# mbmc_single_board.net
KiCad netlist of a schematic drawn in EAGLE
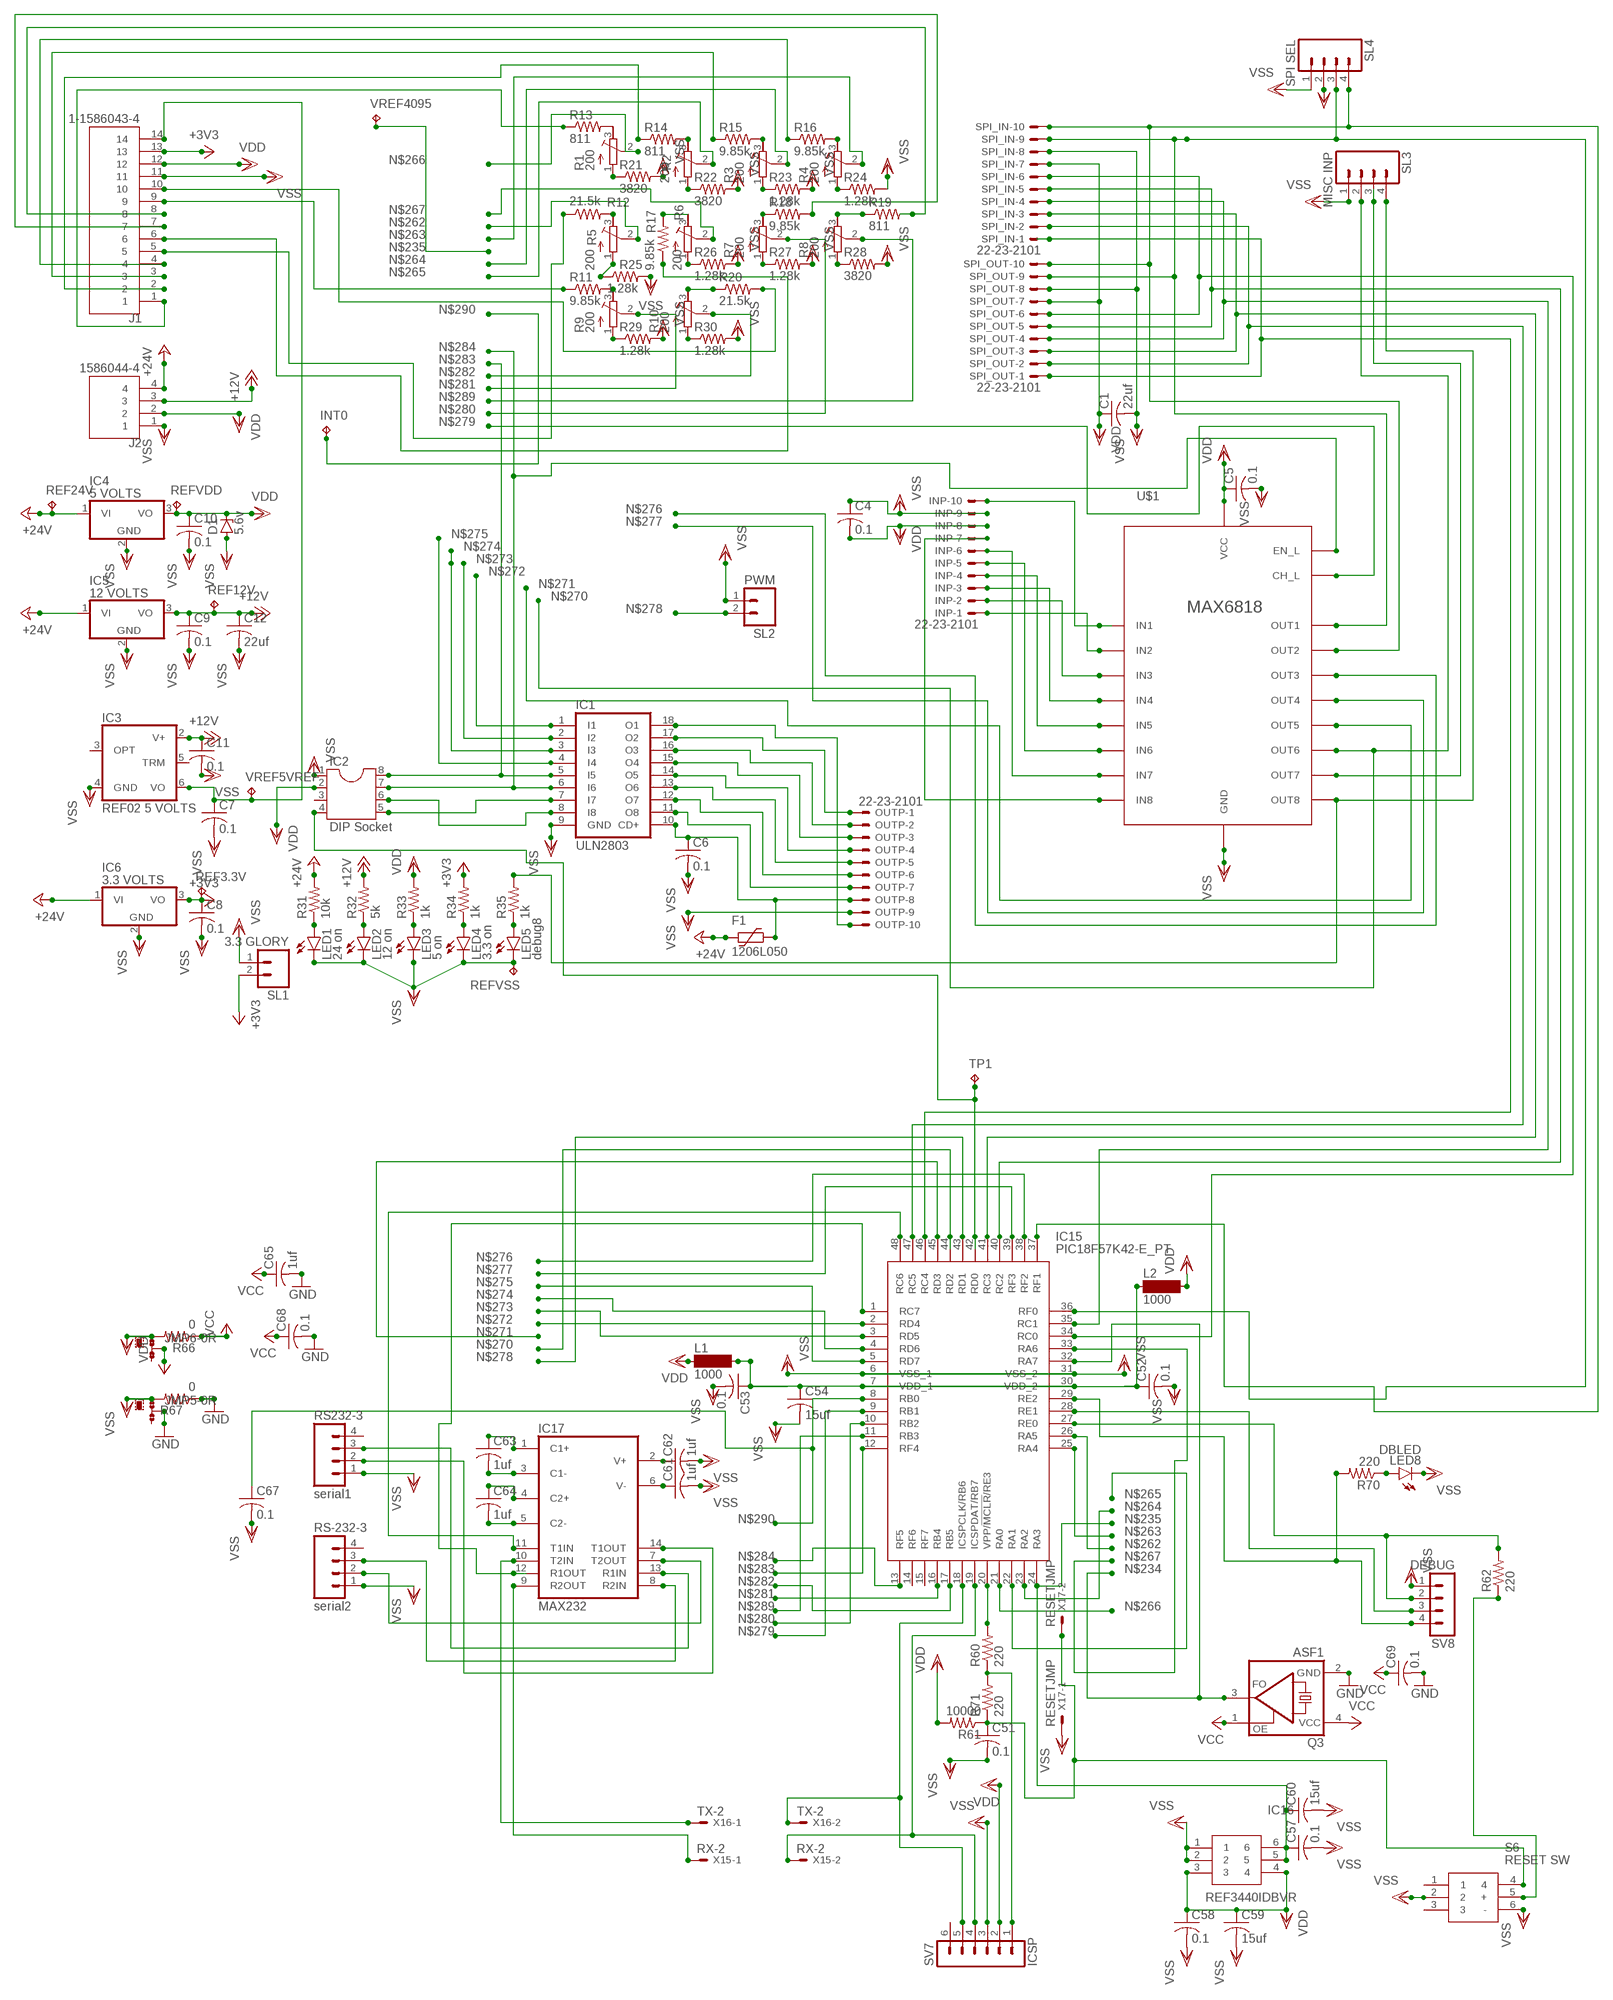
[diagram p0: schematic, sheet 1]

(export (version "E")
  (design (tool "Eeschema 10.0.6"))
  (components
    (comp (ref "C1")
      (value "22uf")
      (footprint "eagle-import:C0805")
      (libsource (lib "eagle-import") (part "C-USC0805"))
    )
    (comp (ref "C4")
      (value "0.1")
      (footprint "eagle-import:C0805")
      (libsource (lib "eagle-import") (part "C-USC0805"))
    )
    (comp (ref "C5")
      (value "0.1")
      (footprint "eagle-import:C0805")
      (libsource (lib "eagle-import") (part "C-USC0805"))
    )
    (comp (ref "C6")
      (value "0.1")
      (footprint "eagle-import:C0805")
      (libsource (lib "eagle-import") (part "C-USC0805"))
    )
    (comp (ref "C7")
      (value "0.1")
      (footprint "eagle-import:C0805")
      (libsource (lib "eagle-import") (part "C-USC0805"))
    )
    (comp (ref "C8")
      (value "0.1")
      (footprint "eagle-import:C0805")
      (libsource (lib "eagle-import") (part "C-USC0805"))
    )
    (comp (ref "C9")
      (value "0.1")
      (footprint "eagle-import:C0805")
      (libsource (lib "eagle-import") (part "C-USC0805"))
    )
    (comp (ref "C10")
      (value "0.1")
      (footprint "eagle-import:C0805")
      (libsource (lib "eagle-import") (part "C-USC0805"))
    )
    (comp (ref "C11")
      (value "0.1")
      (footprint "eagle-import:C0805")
      (libsource (lib "eagle-import") (part "C-USC0805"))
    )
    (comp (ref "C12")
      (value "22uf")
      (footprint "eagle-import:C0805")
      (libsource (lib "eagle-import") (part "C-USC0805"))
    )
    (comp (ref "C51")
      (value "0.1")
      (footprint "eagle-import:C1206")
      (libsource (lib "eagle-import") (part "C-USC1206"))
    )
    (comp (ref "C52")
      (value "0.1")
      (footprint "eagle-import:C1206")
      (libsource (lib "eagle-import") (part "C-USC1206"))
    )
    (comp (ref "C53")
      (value "0.1")
      (footprint "eagle-import:C1206")
      (libsource (lib "eagle-import") (part "C-USC1206"))
    )
    (comp (ref "C54")
      (value "15uf")
      (footprint "eagle-import:C1206")
      (libsource (lib "eagle-import") (part "C-USC1206"))
    )
    (comp (ref "C57")
      (value "0.1")
      (footprint "eagle-import:C1206")
      (libsource (lib "eagle-import") (part "C-USC1206"))
    )
    (comp (ref "C58")
      (value "0.1")
      (footprint "eagle-import:C1206")
      (libsource (lib "eagle-import") (part "C-USC1206"))
    )
    (comp (ref "C59")
      (value "15uf")
      (footprint "eagle-import:C1206")
      (libsource (lib "eagle-import") (part "C-USC1206"))
    )
    (comp (ref "C60")
      (value "15uf")
      (footprint "eagle-import:C1206")
      (libsource (lib "eagle-import") (part "C-USC1206"))
    )
    (comp (ref "C61")
      (value "1uf")
      (footprint "eagle-import:C0805")
      (libsource (lib "eagle-import") (part "C-USC0805"))
    )
    (comp (ref "C62")
      (value "1uf")
      (footprint "eagle-import:C0805")
      (libsource (lib "eagle-import") (part "C-USC0805"))
    )
    (comp (ref "C63")
      (value "1uf")
      (footprint "eagle-import:C0805")
      (libsource (lib "eagle-import") (part "C-USC0805"))
    )
    (comp (ref "C64")
      (value "1uf")
      (footprint "eagle-import:C0805")
      (libsource (lib "eagle-import") (part "C-USC0805"))
    )
    (comp (ref "C65")
      (value "1uf")
      (footprint "eagle-import:C0805")
      (libsource (lib "eagle-import") (part "C-USC0805"))
    )
    (comp (ref "C67")
      (value "0.1")
      (footprint "eagle-import:C1206")
      (libsource (lib "eagle-import") (part "C-USC1206"))
    )
    (comp (ref "C68")
      (value "0.1")
      (footprint "eagle-import:C1206")
      (libsource (lib "eagle-import") (part "C-USC1206"))
    )
    (comp (ref "C69")
      (value "0.1")
      (footprint "eagle-import:C1206")
      (libsource (lib "eagle-import") (part "C-USC1206"))
    )
    (comp (ref "D1")
      (value "5.6v")
      (footprint "eagle-import:ZDIO-2.5")
      (libsource (lib "eagle-import") (part "ZENER-DIODEZD-2.5"))
    )
    (comp (ref "F1")
      (value "1206L050")
      (footprint "eagle-import:1206L")
      (fields (field (name "MF") "Littelfuse"))
      (libsource (lib "eagle-import") (part "?1206L050"))
    )
    (comp (ref "IC1")
      (value "ULN2803")
      (footprint "eagle-import:DIL18")
      (libsource (lib "eagle-import") (part "ULN2803A"))
    )
    (comp (ref "IC2")
      (value "DIP Socket")
      (footprint "eagle-import:SOCKET-08")
      (libsource (lib "eagle-import") (part "DIL8S"))
    )
    (comp (ref "IC3")
      (value "REF02 5 VOLTS")
      (footprint "eagle-import:DIL08")
      (libsource (lib "eagle-import") (part "REF02Z"))
    )
    (comp (ref "IC4")
      (value "5 VOLTS")
      (footprint "eagle-import:TO220V")
      (libsource (lib "eagle-import") (part "78TV05"))
    )
    (comp (ref "IC5")
      (value "12 VOLTS")
      (footprint "eagle-import:TO220V")
      (libsource (lib "eagle-import") (part "78TV05"))
    )
    (comp (ref "IC6")
      (value "3.3 VOLTS")
      (footprint "eagle-import:TO220V")
      (libsource (lib "eagle-import") (part "78TV05"))
    )
    (comp (ref "IC15")
      (value "PIC18F57K42-E_PT")
      (footprint "eagle-import:QFP50P900X900X120-48N")
      (fields
        (field (name "MANUFACTURER_PART_NUMBER") "PIC18F57K42-E/PT")
        (field (name "MOUSER_PART_NUMBER") "579-PIC18F57K42-E/PT")
      )
      (libsource (lib "eagle-import") (part "PIC18F57K42-E_PT"))
    )
    (comp (ref "IC16")
      (value "REF3440IDBVR")
      (footprint "eagle-import:SOP95P280X145-6N")
      (libsource (lib "eagle-import") (part "REF3440IDBVR"))
    )
    (comp (ref "IC17")
      (value "MAX232")
      (footprint "eagle-import:DIL16")
      (fields (field (name "MF") "MAXIM") (field (name "MPN") "MAX232ACPE+"))
      (libsource (lib "eagle-import") (part "MAX232"))
    )
    (comp (ref "INP")
      (value "22-23-2101")
      (footprint "eagle-import:22-23-2101")
      (fields (field (name "MF") "MOLEX"))
      (libsource (lib "eagle-import") (part "22-23-2101"))
    )
    (comp (ref "INT0")
      (value "TPB1,27")
      (footprint "eagle-import:B1,27")
      (libsource (lib "eagle-import") (part "TPB1,27"))
    )
    (comp (ref "J1")
      (value "1-1586043-4")
      (footprint "eagle-import:TE_1-1586043-4")
      (fields (field (name "MANUFACTURER") "TE"))
      (libsource (lib "eagle-import") (part "1-1586043-4"))
    )
    (comp (ref "J2")
      (value "1586044-4")
      (footprint "eagle-import:TE_1586044-4")
      (fields (field (name "MANUFACTURER") "TE"))
      (libsource (lib "eagle-import") (part "1586044-4"))
    )
    (comp (ref "JMP5")
      (value "0R-JUMPA")
      (footprint "eagle-import:A0R-JMP")
      (libsource (lib "eagle-import") (part "0R-JUMPA"))
    )
    (comp (ref "JMP6")
      (value "0R-JUMPA")
      (footprint "eagle-import:A0R-JMP")
      (libsource (lib "eagle-import") (part "0R-JUMPA"))
    )
    (comp (ref "L1")
      (value "1000")
      (footprint "eagle-import:SM-1206")
      (libsource (lib "eagle-import") (part "SM-1206"))
    )
    (comp (ref "L2")
      (value "1000")
      (footprint "eagle-import:SM-1206")
      (libsource (lib "eagle-import") (part "SM-1206"))
    )
    (comp (ref "LED1")
      (value "24 on")
      (footprint "eagle-import:CHIPLED_1206")
      (libsource (lib "eagle-import") (part "LEDCHIPLED_1206"))
    )
    (comp (ref "LED2")
      (value "12 on")
      (footprint "eagle-import:CHIPLED_1206")
      (libsource (lib "eagle-import") (part "LEDCHIPLED_1206"))
    )
    (comp (ref "LED3")
      (value "5 on")
      (footprint "eagle-import:CHIPLED_1206")
      (libsource (lib "eagle-import") (part "LEDCHIPLED_1206"))
    )
    (comp (ref "LED4")
      (value "3.3 on")
      (footprint "eagle-import:CHIPLED_1206")
      (libsource (lib "eagle-import") (part "LEDCHIPLED_1206"))
    )
    (comp (ref "LED5")
      (value "debug8")
      (footprint "eagle-import:CHIPLED_1206")
      (libsource (lib "eagle-import") (part "LEDCHIPLED_1206"))
    )
    (comp (ref "LED8")
      (value "DBLED")
      (footprint "eagle-import:CHIPLED_1206")
      (libsource (lib "eagle-import") (part "LEDCHIPLED_1206"))
    )
    (comp (ref "OUTP")
      (value "22-23-2101")
      (footprint "eagle-import:22-23-2101")
      (fields (field (name "MF") "MOLEX"))
      (libsource (lib "eagle-import") (part "22-23-2101"))
    )
    (comp (ref "Q3")
      (value "ASF1")
      (footprint "eagle-import:ASF")
      (libsource (lib "eagle-import") (part "ASF1"))
    )
    (comp (ref "R1")
      (value "200")
      (footprint "eagle-import:RTRIM3339P")
      (libsource (lib "eagle-import") (part "R-TRIMM3339P"))
    )
    (comp (ref "R2")
      (value "200")
      (footprint "eagle-import:RTRIM3339P")
      (libsource (lib "eagle-import") (part "R-TRIMM3339P"))
    )
    (comp (ref "R3")
      (value "200")
      (footprint "eagle-import:RTRIM3339P")
      (libsource (lib "eagle-import") (part "R-TRIMM3339P"))
    )
    (comp (ref "R4")
      (value "200")
      (footprint "eagle-import:RTRIM3339P")
      (libsource (lib "eagle-import") (part "R-TRIMM3339P"))
    )
    (comp (ref "R5")
      (value "200")
      (footprint "eagle-import:RTRIM3339P")
      (libsource (lib "eagle-import") (part "R-TRIMM3339P"))
    )
    (comp (ref "R6")
      (value "200")
      (footprint "eagle-import:RTRIM3339P")
      (libsource (lib "eagle-import") (part "R-TRIMM3339P"))
    )
    (comp (ref "R7")
      (value "200")
      (footprint "eagle-import:RTRIM3339P")
      (libsource (lib "eagle-import") (part "R-TRIMM3339P"))
    )
    (comp (ref "R8")
      (value "200")
      (footprint "eagle-import:RTRIM3339P")
      (libsource (lib "eagle-import") (part "R-TRIMM3339P"))
    )
    (comp (ref "R9")
      (value "200")
      (footprint "eagle-import:RTRIM3339P")
      (libsource (lib "eagle-import") (part "R-TRIMM3339P"))
    )
    (comp (ref "R10")
      (value "200")
      (footprint "eagle-import:RTRIM3339P")
      (libsource (lib "eagle-import") (part "R-TRIMM3339P"))
    )
    (comp (ref "R11")
      (value "9.85k")
      (footprint "eagle-import:R0805")
      (libsource (lib "eagle-import") (part "R-US_R0805"))
    )
    (comp (ref "R12")
      (value "21.5k")
      (footprint "eagle-import:R0805")
      (libsource (lib "eagle-import") (part "R-US_R0805"))
    )
    (comp (ref "R13")
      (value "811")
      (footprint "eagle-import:R0805")
      (libsource (lib "eagle-import") (part "R-US_R0805"))
    )
    (comp (ref "R14")
      (value "811")
      (footprint "eagle-import:R0805")
      (libsource (lib "eagle-import") (part "R-US_R0805"))
    )
    (comp (ref "R15")
      (value "9.85k")
      (footprint "eagle-import:R0805")
      (libsource (lib "eagle-import") (part "R-US_R0805"))
    )
    (comp (ref "R16")
      (value "9.85k")
      (footprint "eagle-import:R0805")
      (libsource (lib "eagle-import") (part "R-US_R0805"))
    )
    (comp (ref "R17")
      (value "9.85k")
      (footprint "eagle-import:R0805")
      (libsource (lib "eagle-import") (part "R-US_R0805"))
    )
    (comp (ref "R18")
      (value "9.85k")
      (footprint "eagle-import:R0805")
      (libsource (lib "eagle-import") (part "R-US_R0805"))
    )
    (comp (ref "R19")
      (value "811")
      (footprint "eagle-import:R0805")
      (libsource (lib "eagle-import") (part "R-US_R0805"))
    )
    (comp (ref "R20")
      (value "21.5k")
      (footprint "eagle-import:R0805")
      (libsource (lib "eagle-import") (part "R-US_R0805"))
    )
    (comp (ref "R21")
      (value "3820")
      (footprint "eagle-import:R0805")
      (libsource (lib "eagle-import") (part "R-US_R0805"))
    )
    (comp (ref "R22")
      (value "3820")
      (footprint "eagle-import:R0805")
      (libsource (lib "eagle-import") (part "R-US_R0805"))
    )
    (comp (ref "R23")
      (value "1.28k")
      (footprint "eagle-import:R0805")
      (libsource (lib "eagle-import") (part "R-US_R0805"))
    )
    (comp (ref "R24")
      (value "1.28k")
      (footprint "eagle-import:R0805")
      (libsource (lib "eagle-import") (part "R-US_R0805"))
    )
    (comp (ref "R25")
      (value "1.28k")
      (footprint "eagle-import:R0805")
      (libsource (lib "eagle-import") (part "R-US_R0805"))
    )
    (comp (ref "R26")
      (value "1.28k")
      (footprint "eagle-import:R0805")
      (libsource (lib "eagle-import") (part "R-US_R0805"))
    )
    (comp (ref "R27")
      (value "1.28k")
      (footprint "eagle-import:R0805")
      (libsource (lib "eagle-import") (part "R-US_R0805"))
    )
    (comp (ref "R28")
      (value "3820")
      (footprint "eagle-import:R0805")
      (libsource (lib "eagle-import") (part "R-US_R0805"))
    )
    (comp (ref "R29")
      (value "1.28k")
      (footprint "eagle-import:R0805")
      (libsource (lib "eagle-import") (part "R-US_R0805"))
    )
    (comp (ref "R30")
      (value "1.28k")
      (footprint "eagle-import:R0805")
      (libsource (lib "eagle-import") (part "R-US_R0805"))
    )
    (comp (ref "R31")
      (value "10k")
      (footprint "eagle-import:R0805")
      (libsource (lib "eagle-import") (part "R-US_R0805"))
    )
    (comp (ref "R32")
      (value "5k")
      (footprint "eagle-import:R0805")
      (libsource (lib "eagle-import") (part "R-US_R0805"))
    )
    (comp (ref "R33")
      (value "1k")
      (footprint "eagle-import:R0805")
      (libsource (lib "eagle-import") (part "R-US_R0805"))
    )
    (comp (ref "R34")
      (value "1k")
      (footprint "eagle-import:R0805")
      (libsource (lib "eagle-import") (part "R-US_R0805"))
    )
    (comp (ref "R35")
      (value "1k")
      (footprint "eagle-import:R0805")
      (libsource (lib "eagle-import") (part "R-US_R0805"))
    )
    (comp (ref "R60")
      (value "220")
      (footprint "eagle-import:R1206")
      (libsource (lib "eagle-import") (part "R-US_R1206"))
    )
    (comp (ref "R61")
      (value "10000")
      (footprint "eagle-import:R1206")
      (libsource (lib "eagle-import") (part "R-US_R1206"))
    )
    (comp (ref "R62")
      (value "220")
      (footprint "eagle-import:R1206")
      (libsource (lib "eagle-import") (part "R-US_R1206"))
    )
    (comp (ref "R66")
      (value "0")
      (footprint "eagle-import:R1206")
      (libsource (lib "eagle-import") (part "R-US_R1206"))
    )
    (comp (ref "R67")
      (value "0")
      (footprint "eagle-import:R1206")
      (libsource (lib "eagle-import") (part "R-US_R1206"))
    )
    (comp (ref "R70")
      (value "220")
      (footprint "eagle-import:R1206")
      (libsource (lib "eagle-import") (part "R-US_R1206"))
    )
    (comp (ref "R71")
      (value "220")
      (footprint "eagle-import:R1206")
      (libsource (lib "eagle-import") (part "R-US_R1206"))
    )
    (comp (ref "REF3.3V")
      (value "TPB1,27")
      (footprint "eagle-import:B1,27")
      (libsource (lib "eagle-import") (part "TPB1,27"))
    )
    (comp (ref "REF12V")
      (value "TPB1,27")
      (footprint "eagle-import:B1,27")
      (libsource (lib "eagle-import") (part "TPB1,27"))
    )
    (comp (ref "REF24V")
      (value "TPB1,27")
      (footprint "eagle-import:B1,27")
      (libsource (lib "eagle-import") (part "TPB1,27"))
    )
    (comp (ref "REFVDD")
      (value "TPB1,27")
      (footprint "eagle-import:B1,27")
      (libsource (lib "eagle-import") (part "TPB1,27"))
    )
    (comp (ref "REFVSS")
      (value "TPB1,27")
      (footprint "eagle-import:B1,27")
      (libsource (lib "eagle-import") (part "TPB1,27"))
    )
    (comp (ref "RS-232-3")
      (value "serial2")
      (footprint "eagle-import:04P")
      (libsource (lib "eagle-import") (part "M04"))
    )
    (comp (ref "RS232-3")
      (value "serial1")
      (footprint "eagle-import:04P")
      (libsource (lib "eagle-import") (part "M04"))
    )
    (comp (ref "S6")
      (value "RESET SW")
      (footprint "eagle-import:B3W-9_1-LED")
      (fields
        (field (name "MANUFACTURER_PART_NUMBER") "B3W-9000-Y1N")
        (field (name "MOUSER_PART_NUMBER") "653-B3W-9000-Y1N")
        (field (name "RS_PART_NUMBER") "0492777P")
      )
      (libsource (lib "eagle-import") (part "B3W-9000-Y1N"))
    )
    (comp (ref "SL1")
      (value "3.3 GLORY")
      (footprint "eagle-import:02P")
      (libsource (lib "eagle-import") (part "M02"))
    )
    (comp (ref "SL2")
      (value "PWM")
      (footprint "eagle-import:02P")
      (libsource (lib "eagle-import") (part "M02"))
    )
    (comp (ref "SL3")
      (value "MISC INP")
      (footprint "eagle-import:04P")
      (libsource (lib "eagle-import") (part "M04"))
    )
    (comp (ref "SL4")
      (value "SPI SEL")
      (footprint "eagle-import:04P")
      (libsource (lib "eagle-import") (part "M04"))
    )
    (comp (ref "SPI_IN")
      (value "22-23-2101")
      (footprint "eagle-import:22-23-2101")
      (fields (field (name "MF") "MOLEX"))
      (libsource (lib "eagle-import") (part "22-23-2101"))
    )
    (comp (ref "SPI_OUT")
      (value "22-23-2101")
      (footprint "eagle-import:22-23-2101")
      (fields (field (name "MF") "MOLEX"))
      (libsource (lib "eagle-import") (part "22-23-2101"))
    )
    (comp (ref "SV7")
      (value "ICSP")
      (footprint "eagle-import:MA06-1")
      (libsource (lib "eagle-import") (part "MA06-1"))
    )
    (comp (ref "SV8")
      (value "DEBUG")
      (footprint "eagle-import:MA04-1")
      (libsource (lib "eagle-import") (part "MA04-1"))
    )
    (comp (ref "TP1")
      (value "TPB1,27")
      (footprint "eagle-import:B1,27")
      (libsource (lib "eagle-import") (part "TPB1,27"))
    )
    (comp (ref "U$1")
      (value "MAX6818")
      (footprint "eagle-import:SSOP20")
      (fields (field (name "MF") "Maxim Integrated"))
      (libsource (lib "eagle-import") (part "MAX6818"))
    )
    (comp (ref "VREF5VREF")
      (value "TPB1,27")
      (footprint "eagle-import:B1,27")
      (libsource (lib "eagle-import") (part "TPB1,27"))
    )
    (comp (ref "VREF4095")
      (value "TPB1,27")
      (footprint "eagle-import:B1,27")
      (libsource (lib "eagle-import") (part "TPB1,27"))
    )
    (comp (ref "X15")
      (value "RX-2")
      (footprint "eagle-import:332-02")
      (libsource (lib "eagle-import") (part "332-02"))
    )
    (comp (ref "X16")
      (value "TX-2")
      (footprint "eagle-import:332-02")
      (libsource (lib "eagle-import") (part "332-02"))
    )
    (comp (ref "X17")
      (value "RESETJMP")
      (footprint "eagle-import:332-02")
      (libsource (lib "eagle-import") (part "332-02"))
    )
  )
  (nets
    (net (code "1") (name "+3V3") (class "Default")
      (node (ref "C8") (pin "1") (pinfunction "1_1") (pintype "passive"))
      (node (ref "IC6") (pin "3") (pinfunction "VO_3") (pintype "passive"))
      (node (ref "J1") (pin "13") (pinfunction "13_13") (pintype "passive"))
      (node (ref "R34") (pin "2") (pinfunction "2_2") (pintype "passive"))
      (node (ref "REF3.3V") (pin "TP") (pinfunction "TP_TP") (pintype "input"))
      (node (ref "SL1") (pin "2") (pinfunction "2_2") (pintype "passive"))
    )
    (net (code "2") (name "+12V") (class "Default")
      (node (ref "C11") (pin "1") (pinfunction "1_1") (pintype "passive"))
      (node (ref "C12") (pin "1") (pinfunction "1_1") (pintype "passive"))
      (node (ref "C9") (pin "1") (pinfunction "1_1") (pintype "passive"))
      (node (ref "IC3") (pin "2") (pinfunction "V+_2") (pintype "power_in"))
      (node (ref "IC5") (pin "3") (pinfunction "VO_3") (pintype "passive"))
      (node (ref "J2") (pin "3") (pinfunction "3_3") (pintype "passive"))
      (node (ref "R32") (pin "2") (pinfunction "2_2") (pintype "passive"))
      (node (ref "REF12V") (pin "TP") (pinfunction "TP_TP") (pintype "input"))
    )
    (net (code "3") (name "+24V") (class "Default")
      (node (ref "F1") (pin "2") (pinfunction "2_2") (pintype "passive"))
      (node (ref "IC4") (pin "1") (pinfunction "VI_1") (pintype "input"))
      (node (ref "IC5") (pin "1") (pinfunction "VI_1") (pintype "input"))
      (node (ref "IC6") (pin "1") (pinfunction "VI_1") (pintype "input"))
      (node (ref "J2") (pin "4") (pinfunction "4_4") (pintype "passive"))
      (node (ref "R31") (pin "2") (pinfunction "2_2") (pintype "passive"))
      (node (ref "REF24V") (pin "TP") (pinfunction "TP_TP") (pintype "input"))
    )
    (net (code "4") (name "/N$234") (class "Default")
      (node (ref "IC15") (pin "32") (pinfunction "RA7_32") (pintype "bidirectional"))
      (node (ref "Q3") (pin "3") (pinfunction "FO_3") (pintype "output"))
    )
    (net (code "5") (name "/N$235") (class "Default")
      (node (ref "C57") (pin "1") (pinfunction "1_1") (pintype "passive"))
      (node (ref "C60") (pin "1") (pinfunction "1_1") (pintype "passive"))
      (node (ref "IC15") (pin "24") (pinfunction "RA3_24") (pintype "bidirectional"))
      (node (ref "IC16") (pin "5") (pinfunction "5_5") (pintype "bidirectional"))
      (node (ref "IC16") (pin "6") (pinfunction "6_6") (pintype "bidirectional"))
      (node (ref "VREF4095") (pin "TP") (pinfunction "TP_TP") (pintype "input"))
    )
    (net (code "6") (name "/N$262") (class "Default")
      (node (ref "IC15") (pin "26") (pinfunction "RA5_26") (pintype "bidirectional"))
      (node (ref "R5") (pin "2") (pinfunction "S_2") (pintype "passive"))
    )
    (net (code "7") (name "/N$263") (class "Default")
      (node (ref "IC15") (pin "25") (pinfunction "RA4_25") (pintype "bidirectional"))
      (node (ref "R4") (pin "2") (pinfunction "S_2") (pintype "passive"))
    )
    (net (code "8") (name "/N$264") (class "Default")
      (node (ref "IC15") (pin "23") (pinfunction "RA2_23") (pintype "bidirectional"))
      (node (ref "R3") (pin "2") (pinfunction "S_2") (pintype "passive"))
    )
    (net (code "9") (name "/N$265") (class "Default")
      (node (ref "IC15") (pin "22") (pinfunction "RA1_22") (pintype "bidirectional"))
      (node (ref "R2") (pin "2") (pinfunction "S_2") (pintype "passive"))
    )
    (net (code "10") (name "/N$266") (class "Default")
      (node (ref "IC15") (pin "21") (pinfunction "RA0_21") (pintype "bidirectional"))
      (node (ref "R1") (pin "2") (pinfunction "S_2") (pintype "passive"))
    )
    (net (code "11") (name "/N$267") (class "Default")
      (node (ref "IC15") (pin "33") (pinfunction "RA6_33") (pintype "bidirectional"))
      (node (ref "R6") (pin "2") (pinfunction "S_2") (pintype "passive"))
    )
    (net (code "12") (name "/N$270") (class "Default")
      (node (ref "IC15") (pin "44") (pinfunction "RD2_44") (pintype "bidirectional"))
      (node (ref "SL3") (pin "2") (pinfunction "2_2") (pintype "passive"))
      (node (ref "U$1") (pin "OUT6") (pinfunction "OUT6_OUT6") (pintype "bidirectional"))
    )
    (net (code "13") (name "/N$271") (class "Default")
      (node (ref "IC15") (pin "45") (pinfunction "RD3_45") (pintype "bidirectional"))
      (node (ref "U$1") (pin "OUT5") (pinfunction "OUT5_OUT5") (pintype "bidirectional"))
    )
    (net (code "14") (name "/N$272") (class "Default")
      (node (ref "IC1") (pin "1") (pinfunction "I1_1") (pintype "input"))
      (node (ref "IC15") (pin "2") (pinfunction "RD4_2") (pintype "bidirectional"))
    )
    (net (code "15") (name "/N$273") (class "Default")
      (node (ref "IC1") (pin "2") (pinfunction "I2_2") (pintype "input"))
      (node (ref "IC15") (pin "3") (pinfunction "RD5_3") (pintype "bidirectional"))
    )
    (net (code "16") (name "/N$274") (class "Default")
      (node (ref "IC1") (pin "3") (pinfunction "I3_3") (pintype "input"))
      (node (ref "IC15") (pin "4") (pinfunction "RD6_4") (pintype "bidirectional"))
    )
    (net (code "17") (name "/N$275") (class "Default")
      (node (ref "IC1") (pin "4") (pinfunction "I4_4") (pintype "input"))
      (node (ref "IC15") (pin "5") (pinfunction "RD7_5") (pintype "bidirectional"))
    )
    (net (code "18") (name "/N$276") (class "Default")
      (node (ref "IC15") (pin "38") (pinfunction "RF2_38") (pintype "bidirectional"))
      (node (ref "U$1") (pin "OUT3") (pinfunction "OUT3_OUT3") (pintype "bidirectional"))
    )
    (net (code "19") (name "/N$277") (class "Default")
      (node (ref "IC15") (pin "39") (pinfunction "RF3_39") (pintype "bidirectional"))
      (node (ref "U$1") (pin "OUT4") (pinfunction "OUT4_OUT4") (pintype "bidirectional"))
    )
    (net (code "20") (name "/N$278") (class "Default")
      (node (ref "IC15") (pin "43") (pinfunction "RD1_43") (pintype "bidirectional"))
      (node (ref "SL2") (pin "2") (pinfunction "2_2") (pintype "passive"))
    )
    (net (code "21") (name "/N$279") (class "Default")
      (node (ref "IC15") (pin "9") (pinfunction "RB1_9") (pintype "bidirectional"))
      (node (ref "U$1") (pin "CH_L") (pinfunction "CH_L_CH_L") (pintype "bidirectional"))
    )
    (net (code "22") (name "/N$280") (class "Default")
      (node (ref "IC15") (pin "10") (pinfunction "RB2_10") (pintype "bidirectional"))
      (node (ref "R7") (pin "2") (pinfunction "S_2") (pintype "passive"))
    )
    (net (code "23") (name "/N$281") (class "Default")
      (node (ref "IC15") (pin "16") (pinfunction "RB4_16") (pintype "bidirectional"))
      (node (ref "R9") (pin "2") (pinfunction "S_2") (pintype "passive"))
    )
    (net (code "24") (name "/N$282") (class "Default")
      (node (ref "IC15") (pin "17") (pinfunction "RB5_17") (pintype "bidirectional"))
      (node (ref "R10") (pin "2") (pinfunction "S_2") (pintype "passive"))
    )
    (net (code "25") (name "/N$283") (class "Default")
      (node (ref "IC1") (pin "5") (pinfunction "I5_5") (pintype "input"))
      (node (ref "IC15") (pin "12") (pinfunction "RF4_12") (pintype "bidirectional"))
      (node (ref "IC2") (pin "8") (pinfunction "8_8") (pintype "passive"))
    )
    (net (code "26") (name "/N$284") (class "Default")
      (node (ref "IC1") (pin "6") (pinfunction "I6_6") (pintype "input"))
      (node (ref "IC15") (pin "13") (pinfunction "RF5_13") (pintype "bidirectional"))
      (node (ref "IC2") (pin "7") (pinfunction "7_7") (pintype "passive"))
      (node (ref "U$1") (pin "EN_L") (pinfunction "EN_L_EN_L") (pintype "bidirectional"))
    )
    (net (code "27") (name "/N$289") (class "Default")
      (node (ref "IC15") (pin "11") (pinfunction "RB3_11") (pintype "bidirectional"))
      (node (ref "R8") (pin "2") (pinfunction "S_2") (pintype "passive"))
    )
    (net (code "28") (name "/N$290") (class "Default")
      (node (ref "C67") (pin "1") (pinfunction "1_1") (pintype "passive"))
      (node (ref "IC15") (pin "8") (pinfunction "RB0_8") (pintype "bidirectional"))
      (node (ref "INT0") (pin "TP") (pinfunction "TP_TP") (pintype "input"))
    )
    (net (code "29") (name "GND") (class "Default")
      (node (ref "C65") (pin "2") (pinfunction "2_2") (pintype "passive"))
      (node (ref "C68") (pin "2") (pinfunction "2_2") (pintype "passive"))
      (node (ref "C69") (pin "2") (pinfunction "2_2") (pintype "passive"))
      (node (ref "JMP5") (pin "2") (pinfunction "2_2") (pintype "passive"))
      (node (ref "Q3") (pin "2") (pinfunction "GND_2") (pintype "power_in"))
      (node (ref "R67") (pin "1") (pinfunction "1_1") (pintype "passive"))
    )
    (net (code "30") (name "Net-(IC1-CD+)") (class "Default")
      (node (ref "C6") (pin "1") (pinfunction "1_1") (pintype "passive"))
      (node (ref "F1") (pin "1") (pinfunction "1_1") (pintype "passive"))
      (node (ref "IC1") (pin "10") (pinfunction "CD+_10") (pintype "passive"))
      (node (ref "OUTP") (pin "8") (pinfunction "S_8") (pintype "passive"))
    )
    (net (code "31") (name "Net-(IC1-I7)") (class "Default")
      (node (ref "IC1") (pin "7") (pinfunction "I7_7") (pintype "input"))
      (node (ref "IC2") (pin "5") (pinfunction "5_5") (pintype "passive"))
    )
    (net (code "32") (name "Net-(IC1-I8)") (class "Default")
      (node (ref "IC1") (pin "8") (pinfunction "I8_8") (pintype "input"))
      (node (ref "IC2") (pin "6") (pinfunction "6_6") (pintype "passive"))
    )
    (net (code "33") (name "Net-(IC1-O1)") (class "Default")
      (node (ref "IC1") (pin "18") (pinfunction "O1_18") (pintype "open_collector"))
      (node (ref "OUTP") (pin "10") (pinfunction "S_10") (pintype "passive"))
    )
    (net (code "34") (name "Net-(IC1-O2)") (class "Default")
      (node (ref "IC1") (pin "17") (pinfunction "O2_17") (pintype "open_collector"))
      (node (ref "OUTP") (pin "1") (pinfunction "S_1") (pintype "passive"))
    )
    (net (code "35") (name "Net-(IC1-O3)") (class "Default")
      (node (ref "IC1") (pin "16") (pinfunction "O3_16") (pintype "open_collector"))
      (node (ref "OUTP") (pin "2") (pinfunction "S_2") (pintype "passive"))
    )
    (net (code "36") (name "Net-(IC1-O4)") (class "Default")
      (node (ref "IC1") (pin "15") (pinfunction "O4_15") (pintype "open_collector"))
      (node (ref "OUTP") (pin "3") (pinfunction "S_3") (pintype "passive"))
    )
    (net (code "37") (name "Net-(IC1-O5)") (class "Default")
      (node (ref "IC1") (pin "14") (pinfunction "O5_14") (pintype "open_collector"))
      (node (ref "OUTP") (pin "4") (pinfunction "S_4") (pintype "passive"))
    )
    (net (code "38") (name "Net-(IC1-O6)") (class "Default")
      (node (ref "IC1") (pin "13") (pinfunction "O6_13") (pintype "open_collector"))
      (node (ref "OUTP") (pin "5") (pinfunction "S_5") (pintype "passive"))
    )
    (net (code "39") (name "Net-(IC1-O7)") (class "Default")
      (node (ref "IC1") (pin "12") (pinfunction "O7_12") (pintype "open_collector"))
      (node (ref "OUTP") (pin "6") (pinfunction "S_6") (pintype "passive"))
    )
    (net (code "40") (name "Net-(IC1-O8)") (class "Default")
      (node (ref "IC1") (pin "11") (pinfunction "O8_11") (pintype "open_collector"))
      (node (ref "OUTP") (pin "7") (pinfunction "S_7") (pintype "passive"))
    )
    (net (code "41") (name "Net-(IC3-VO)") (class "Default")
      (node (ref "C7") (pin "1") (pinfunction "1_1") (pintype "passive"))
      (node (ref "IC3") (pin "6") (pinfunction "VO_6") (pintype "output"))
      (node (ref "J1") (pin "14") (pinfunction "14_14") (pintype "passive"))
      (node (ref "VREF5VREF") (pin "TP") (pinfunction "TP_TP") (pintype "input"))
    )
    (net (code "42") (name "Net-(IC15-ICSPCLK{slash}RB6)") (class "Default")
      (node (ref "IC15") (pin "18") (pinfunction "ICSPCLK/RB6_18") (pintype "bidirectional"))
      (node (ref "SV7") (pin "5") (pinfunction "5_5") (pintype "passive"))
      (node (ref "X16") (pin "2") (pinfunction "S_2") (pintype "passive"))
    )
    (net (code "43") (name "Net-(IC15-ICSPDAT{slash}RB7)") (class "Default")
      (node (ref "IC15") (pin "19") (pinfunction "ICSPDAT/RB7_19") (pintype "bidirectional"))
      (node (ref "SV7") (pin "4") (pinfunction "4_4") (pintype "passive"))
      (node (ref "X15") (pin "2") (pinfunction "S_2") (pintype "passive"))
    )
    (net (code "44") (name "Net-(IC15-RC0)") (class "Default")
      (node (ref "IC15") (pin "34") (pinfunction "RC0_34") (pintype "bidirectional"))
      (node (ref "SPI_IN") (pin "6") (pinfunction "S_6") (pintype "passive"))
      (node (ref "SPI_OUT") (pin "6") (pinfunction "S_6") (pintype "passive"))
    )
    (net (code "45") (name "Net-(IC15-RC1)") (class "Default")
      (node (ref "IC15") (pin "35") (pinfunction "RC1_35") (pintype "bidirectional"))
      (node (ref "SPI_IN") (pin "4") (pinfunction "S_4") (pintype "passive"))
      (node (ref "SPI_OUT") (pin "4") (pinfunction "S_4") (pintype "passive"))
    )
    (net (code "46") (name "Net-(IC15-RC2)") (class "Default")
      (node (ref "IC15") (pin "40") (pinfunction "RC2_40") (pintype "bidirectional"))
      (node (ref "SPI_IN") (pin "5") (pinfunction "S_5") (pintype "passive"))
      (node (ref "SPI_OUT") (pin "5") (pinfunction "S_5") (pintype "passive"))
    )
    (net (code "47") (name "Net-(IC15-RC3)") (class "Default")
      (node (ref "IC15") (pin "41") (pinfunction "RC3_41") (pintype "bidirectional"))
      (node (ref "SPI_IN") (pin "3") (pinfunction "S_3") (pintype "passive"))
      (node (ref "SPI_OUT") (pin "3") (pinfunction "S_3") (pintype "passive"))
    )
    (net (code "48") (name "Net-(IC15-RC4)") (class "Default")
      (node (ref "IC15") (pin "46") (pinfunction "RC4_46") (pintype "bidirectional"))
      (node (ref "SPI_IN") (pin "1") (pinfunction "S_1") (pintype "passive"))
      (node (ref "SPI_OUT") (pin "1") (pinfunction "S_1") (pintype "passive"))
    )
    (net (code "49") (name "Net-(IC15-RC5)") (class "Default")
      (node (ref "IC15") (pin "47") (pinfunction "RC5_47") (pintype "bidirectional"))
      (node (ref "SPI_IN") (pin "2") (pinfunction "S_2") (pintype "passive"))
      (node (ref "SPI_OUT") (pin "2") (pinfunction "S_2") (pintype "passive"))
    )
    (net (code "50") (name "Net-(IC15-RC6)") (class "Default")
      (node (ref "IC15") (pin "48") (pinfunction "RC6_48") (pintype "bidirectional"))
      (node (ref "IC17") (pin "11") (pinfunction "T1IN_11") (pintype "input"))
    )
    (net (code "51") (name "Net-(IC15-RC7)") (class "Default")
      (node (ref "IC15") (pin "1") (pinfunction "RC7_1") (pintype "bidirectional"))
      (node (ref "IC17") (pin "12") (pinfunction "R1OUT_12") (pintype "output"))
    )
    (net (code "52") (name "Net-(IC15-RD0)") (class "Default")
      (node (ref "IC15") (pin "42") (pinfunction "RD0_42") (pintype "bidirectional"))
      (node (ref "IC2") (pin "4") (pinfunction "4_4") (pintype "passive"))
      (node (ref "TP1") (pin "TP") (pinfunction "TP_TP") (pintype "input"))
    )
    (net (code "53") (name "Net-(IC15-RE0)") (class "Default")
      (node (ref "IC15") (pin "27") (pinfunction "RE0_27") (pintype "bidirectional"))
      (node (ref "R62") (pin "2") (pinfunction "2_2") (pintype "passive"))
      (node (ref "SV8") (pin "2") (pinfunction "2_2") (pintype "passive"))
    )
    (net (code "54") (name "Net-(IC15-RE1)") (class "Default")
      (node (ref "IC15") (pin "28") (pinfunction "RE1_28") (pintype "bidirectional"))
      (node (ref "SV8") (pin "3") (pinfunction "3_3") (pintype "passive"))
    )
    (net (code "55") (name "Net-(IC15-RE2)") (class "Default")
      (node (ref "IC15") (pin "29") (pinfunction "RE2_29") (pintype "bidirectional"))
      (node (ref "R70") (pin "2") (pinfunction "2_2") (pintype "passive"))
      (node (ref "SV8") (pin "4") (pinfunction "4_4") (pintype "passive"))
    )
    (net (code "56") (name "Net-(IC15-RF0)") (class "Default")
      (node (ref "IC15") (pin "36") (pinfunction "RF0_36") (pintype "bidirectional"))
      (node (ref "SL4") (pin "3") (pinfunction "3_3") (pintype "passive"))
      (node (ref "SPI_IN") (pin "9") (pinfunction "S_9") (pintype "passive"))
      (node (ref "SPI_OUT") (pin "9") (pinfunction "S_9") (pintype "passive"))
      (node (ref "U$1") (pin "OUT1") (pinfunction "OUT1_OUT1") (pintype "bidirectional"))
    )
    (net (code "57") (name "Net-(IC15-RF1)") (class "Default")
      (node (ref "IC15") (pin "37") (pinfunction "RF1_37") (pintype "bidirectional"))
      (node (ref "SL4") (pin "4") (pinfunction "4_4") (pintype "passive"))
      (node (ref "SPI_IN") (pin "10") (pinfunction "S_10") (pintype "passive"))
      (node (ref "SPI_OUT") (pin "10") (pinfunction "S_10") (pintype "passive"))
      (node (ref "U$1") (pin "OUT2") (pinfunction "OUT2_OUT2") (pintype "bidirectional"))
    )
    (net (code "58") (name "Net-(IC15-VDD_1)") (class "Default")
      (node (ref "C52") (pin "1") (pinfunction "1_1") (pintype "passive"))
      (node (ref "C53") (pin "1") (pinfunction "1_1") (pintype "passive"))
      (node (ref "C54") (pin "1") (pinfunction "1_1") (pintype "passive"))
      (node (ref "IC15") (pin "30") (pinfunction "VDD_2_30") (pintype "bidirectional"))
      (node (ref "IC15") (pin "7") (pinfunction "VDD_1_7") (pintype "bidirectional"))
      (node (ref "L1") (pin "2") (pinfunction "2_2") (pintype "passive"))
      (node (ref "L2") (pin "1") (pinfunction "1_1") (pintype "passive"))
    )
    (net (code "59") (name "Net-(IC15-VPP{slash}~{MCLR}{slash}RE3)") (class "Default")
      (node (ref "IC15") (pin "20") (pinfunction "VPP/~{MCLR}/RE3_20") (pintype "bidirectional"))
      (node (ref "R60") (pin "2") (pinfunction "2_2") (pintype "passive"))
    )
    (net (code "60") (name "Net-(IC17A-C1+)") (class "Default")
      (node (ref "C63") (pin "1") (pinfunction "1_1") (pintype "passive"))
      (node (ref "IC17") (pin "1") (pinfunction "C1+_1") (pintype "bidirectional"))
    )
    (net (code "61") (name "Net-(IC17A-C1-)") (class "Default")
      (node (ref "C63") (pin "2") (pinfunction "2_2") (pintype "passive"))
      (node (ref "IC17") (pin "3") (pinfunction "C1-_3") (pintype "bidirectional"))
    )
    (net (code "62") (name "Net-(IC17A-C2+)") (class "Default")
      (node (ref "C64") (pin "1") (pinfunction "1_1") (pintype "passive"))
      (node (ref "IC17") (pin "4") (pinfunction "C2+_4") (pintype "bidirectional"))
    )
    (net (code "63") (name "Net-(IC17A-C2-)") (class "Default")
      (node (ref "C64") (pin "2") (pinfunction "2_2") (pintype "passive"))
      (node (ref "IC17") (pin "5") (pinfunction "C2-_5") (pintype "bidirectional"))
    )
    (net (code "64") (name "Net-(IC17A-R1IN)") (class "Default")
      (node (ref "IC17") (pin "13") (pinfunction "R1IN_13") (pintype "input"))
      (node (ref "RS232-3") (pin "3") (pinfunction "3_3") (pintype "passive"))
    )
    (net (code "65") (name "Net-(IC17A-R2IN)") (class "Default")
      (node (ref "IC17") (pin "8") (pinfunction "R2IN_8") (pintype "input"))
      (node (ref "RS-232-3") (pin "3") (pinfunction "3_3") (pintype "passive"))
    )
    (net (code "66") (name "Net-(IC17A-R2OUT)") (class "Default")
      (node (ref "IC17") (pin "9") (pinfunction "R2OUT_9") (pintype "output"))
      (node (ref "X15") (pin "1") (pinfunction "S_1") (pintype "passive"))
    )
    (net (code "67") (name "Net-(IC17A-T1OUT)") (class "Default")
      (node (ref "IC17") (pin "14") (pinfunction "T1OUT_14") (pintype "output"))
      (node (ref "RS232-3") (pin "2") (pinfunction "2_2") (pintype "passive"))
    )
    (net (code "68") (name "Net-(IC17A-T2IN)") (class "Default")
      (node (ref "IC17") (pin "10") (pinfunction "T2IN_10") (pintype "input"))
      (node (ref "X16") (pin "1") (pinfunction "S_1") (pintype "passive"))
    )
    (net (code "69") (name "Net-(IC17A-T2OUT)") (class "Default")
      (node (ref "IC17") (pin "7") (pinfunction "T2OUT_7") (pintype "output"))
      (node (ref "RS-232-3") (pin "2") (pinfunction "2_2") (pintype "passive"))
    )
    (net (code "70") (name "Net-(IC17A-V+)") (class "Default")
      (node (ref "C62") (pin "1") (pinfunction "1_1") (pintype "passive"))
      (node (ref "IC17") (pin "2") (pinfunction "V+_2") (pintype "bidirectional"))
    )
    (net (code "71") (name "Net-(IC17A-V-)") (class "Default")
      (node (ref "C61") (pin "1") (pinfunction "1_1") (pintype "passive"))
      (node (ref "IC17") (pin "6") (pinfunction "V-_6") (pintype "bidirectional"))
    )
    (net (code "72") (name "Net-(INPA-S)") (class "Default")
      (node (ref "INP") (pin "1") (pinfunction "S_1") (pintype "passive"))
      (node (ref "U$1") (pin "IN2") (pinfunction "IN2_IN2") (pintype "bidirectional"))
    )
    (net (code "73") (name "Net-(INPB-S)") (class "Default")
      (node (ref "INP") (pin "10") (pinfunction "S_10") (pintype "passive"))
      (node (ref "U$1") (pin "IN1") (pinfunction "IN1_IN1") (pintype "bidirectional"))
    )
    (net (code "74") (name "Net-(INPC-S)") (class "Default")
      (node (ref "INP") (pin "2") (pinfunction "S_2") (pintype "passive"))
      (node (ref "U$1") (pin "IN3") (pinfunction "IN3_IN3") (pintype "bidirectional"))
    )
    (net (code "75") (name "Net-(INPD-S)") (class "Default")
      (node (ref "INP") (pin "3") (pinfunction "S_3") (pintype "passive"))
      (node (ref "U$1") (pin "IN4") (pinfunction "IN4_IN4") (pintype "bidirectional"))
    )
    (net (code "76") (name "Net-(INPE-S)") (class "Default")
      (node (ref "INP") (pin "4") (pinfunction "S_4") (pintype "passive"))
      (node (ref "U$1") (pin "IN5") (pinfunction "IN5_IN5") (pintype "bidirectional"))
    )
    (net (code "77") (name "Net-(INPF-S)") (class "Default")
      (node (ref "INP") (pin "5") (pinfunction "S_5") (pintype "passive"))
      (node (ref "U$1") (pin "IN6") (pinfunction "IN6_IN6") (pintype "bidirectional"))
    )
    (net (code "78") (name "Net-(INPG-S)") (class "Default")
      (node (ref "INP") (pin "6") (pinfunction "S_6") (pintype "passive"))
      (node (ref "U$1") (pin "IN7") (pinfunction "IN7_IN7") (pintype "bidirectional"))
    )
    (net (code "79") (name "Net-(INPH-S)") (class "Default")
      (node (ref "INP") (pin "7") (pinfunction "S_7") (pintype "passive"))
      (node (ref "U$1") (pin "IN8") (pinfunction "IN8_IN8") (pintype "bidirectional"))
    )
    (net (code "80") (name "Net-(J1-Pad1)") (class "Default")
      (node (ref "J1") (pin "1") (pinfunction "1_1") (pintype "passive"))
      (node (ref "R13") (pin "1") (pinfunction "1_1") (pintype "passive"))
    )
    (net (code "81") (name "Net-(J1-Pad2)") (class "Default")
      (node (ref "J1") (pin "2") (pinfunction "2_2") (pintype "passive"))
      (node (ref "R14") (pin "1") (pinfunction "1_1") (pintype "passive"))
    )
    (net (code "82") (name "Net-(J1-Pad3)") (class "Default")
      (node (ref "J1") (pin "3") (pinfunction "3_3") (pintype "passive"))
      (node (ref "R15") (pin "1") (pinfunction "1_1") (pintype "passive"))
    )
    (net (code "83") (name "Net-(J1-Pad4)") (class "Default")
      (node (ref "J1") (pin "4") (pinfunction "4_4") (pintype "passive"))
      (node (ref "R16") (pin "1") (pinfunction "1_1") (pintype "passive"))
    )
    (net (code "84") (name "Net-(J1-Pad5)") (class "Default")
      (node (ref "J1") (pin "5") (pinfunction "5_5") (pintype "passive"))
      (node (ref "R12") (pin "1") (pinfunction "1_1") (pintype "passive"))
    )
    (net (code "85") (name "Net-(J1-Pad6)") (class "Default")
      (node (ref "J1") (pin "6") (pinfunction "6_6") (pintype "passive"))
      (node (ref "R17") (pin "1") (pinfunction "1_1") (pintype "passive"))
    )
    (net (code "86") (name "Net-(J1-Pad7)") (class "Default")
      (node (ref "J1") (pin "7") (pinfunction "7_7") (pintype "passive"))
      (node (ref "R18") (pin "2") (pinfunction "2_2") (pintype "passive"))
    )
    (net (code "87") (name "Net-(J1-Pad8)") (class "Default")
      (node (ref "J1") (pin "8") (pinfunction "8_8") (pintype "passive"))
      (node (ref "R19") (pin "2") (pinfunction "2_2") (pintype "passive"))
    )
    (net (code "88") (name "Net-(J1-Pad9)") (class "Default")
      (node (ref "J1") (pin "9") (pinfunction "9_9") (pintype "passive"))
      (node (ref "R11") (pin "1") (pinfunction "1_1") (pintype "passive"))
    )
    (net (code "89") (name "Net-(J1-Pad10)") (class "Default")
      (node (ref "J1") (pin "10") (pinfunction "10_10") (pintype "passive"))
      (node (ref "R20") (pin "2") (pinfunction "2_2") (pintype "passive"))
    )
    (net (code "90") (name "Net-(LED1-PadA)") (class "Default")
      (node (ref "LED1") (pin "A") (pinfunction "A_A") (pintype "passive"))
      (node (ref "R31") (pin "1") (pinfunction "1_1") (pintype "passive"))
    )
    (net (code "91") (name "Net-(LED2-PadA)") (class "Default")
      (node (ref "LED2") (pin "A") (pinfunction "A_A") (pintype "passive"))
      (node (ref "R32") (pin "1") (pinfunction "1_1") (pintype "passive"))
    )
    (net (code "92") (name "Net-(LED3-PadA)") (class "Default")
      (node (ref "LED3") (pin "A") (pinfunction "A_A") (pintype "passive"))
      (node (ref "R33") (pin "1") (pinfunction "1_1") (pintype "passive"))
    )
    (net (code "93") (name "Net-(LED4-PadA)") (class "Default")
      (node (ref "LED4") (pin "A") (pinfunction "A_A") (pintype "passive"))
      (node (ref "R34") (pin "1") (pinfunction "1_1") (pintype "passive"))
    )
    (net (code "94") (name "Net-(LED5-PadA)") (class "Default")
      (node (ref "LED5") (pin "A") (pinfunction "A_A") (pintype "passive"))
      (node (ref "R35") (pin "1") (pinfunction "1_1") (pintype "passive"))
    )
    (net (code "95") (name "Net-(LED8-PadA)") (class "Default")
      (node (ref "LED8") (pin "A") (pinfunction "A_A") (pintype "passive"))
      (node (ref "R70") (pin "1") (pinfunction "1_1") (pintype "passive"))
    )
    (net (code "96") (name "Net-(R1-A)") (class "Default")
      (node (ref "R1") (pin "1") (pinfunction "A_1") (pintype "passive"))
      (node (ref "R21") (pin "1") (pinfunction "1_1") (pintype "passive"))
    )
    (net (code "97") (name "Net-(R1-E)") (class "Default")
      (node (ref "R1") (pin "3") (pinfunction "E_3") (pintype "passive"))
      (node (ref "R13") (pin "2") (pinfunction "2_2") (pintype "passive"))
    )
    (net (code "98") (name "Net-(R2-A)") (class "Default")
      (node (ref "R2") (pin "1") (pinfunction "A_1") (pintype "passive"))
      (node (ref "R22") (pin "1") (pinfunction "1_1") (pintype "passive"))
    )
    (net (code "99") (name "Net-(R2-E)") (class "Default")
      (node (ref "R14") (pin "2") (pinfunction "2_2") (pintype "passive"))
      (node (ref "R2") (pin "3") (pinfunction "E_3") (pintype "passive"))
    )
    (net (code "100") (name "Net-(R3-A)") (class "Default")
      (node (ref "R23") (pin "1") (pinfunction "1_1") (pintype "passive"))
      (node (ref "R3") (pin "1") (pinfunction "A_1") (pintype "passive"))
    )
    (net (code "101") (name "Net-(R3-E)") (class "Default")
      (node (ref "R15") (pin "2") (pinfunction "2_2") (pintype "passive"))
      (node (ref "R3") (pin "3") (pinfunction "E_3") (pintype "passive"))
    )
    (net (code "102") (name "Net-(R4-A)") (class "Default")
      (node (ref "R24") (pin "1") (pinfunction "1_1") (pintype "passive"))
      (node (ref "R4") (pin "1") (pinfunction "A_1") (pintype "passive"))
    )
    (net (code "103") (name "Net-(R4-E)") (class "Default")
      (node (ref "R16") (pin "2") (pinfunction "2_2") (pintype "passive"))
      (node (ref "R4") (pin "3") (pinfunction "E_3") (pintype "passive"))
    )
    (net (code "104") (name "Net-(R5-A)") (class "Default")
      (node (ref "R25") (pin "1") (pinfunction "1_1") (pintype "passive"))
      (node (ref "R5") (pin "1") (pinfunction "A_1") (pintype "passive"))
    )
    (net (code "105") (name "Net-(R5-E)") (class "Default")
      (node (ref "R12") (pin "2") (pinfunction "2_2") (pintype "passive"))
      (node (ref "R5") (pin "3") (pinfunction "E_3") (pintype "passive"))
    )
    (net (code "106") (name "Net-(R6-A)") (class "Default")
      (node (ref "R26") (pin "1") (pinfunction "1_1") (pintype "passive"))
      (node (ref "R6") (pin "1") (pinfunction "A_1") (pintype "passive"))
    )
    (net (code "107") (name "Net-(R6-E)") (class "Default")
      (node (ref "R17") (pin "2") (pinfunction "2_2") (pintype "passive"))
      (node (ref "R6") (pin "3") (pinfunction "E_3") (pintype "passive"))
    )
    (net (code "108") (name "Net-(R7-A)") (class "Default")
      (node (ref "R27") (pin "1") (pinfunction "1_1") (pintype "passive"))
      (node (ref "R7") (pin "1") (pinfunction "A_1") (pintype "passive"))
    )
    (net (code "109") (name "Net-(R7-E)") (class "Default")
      (node (ref "R18") (pin "1") (pinfunction "1_1") (pintype "passive"))
      (node (ref "R7") (pin "3") (pinfunction "E_3") (pintype "passive"))
    )
    (net (code "110") (name "Net-(R8-A)") (class "Default")
      (node (ref "R28") (pin "1") (pinfunction "1_1") (pintype "passive"))
      (node (ref "R8") (pin "1") (pinfunction "A_1") (pintype "passive"))
    )
    (net (code "111") (name "Net-(R8-E)") (class "Default")
      (node (ref "R19") (pin "1") (pinfunction "1_1") (pintype "passive"))
      (node (ref "R8") (pin "3") (pinfunction "E_3") (pintype "passive"))
    )
    (net (code "112") (name "Net-(R9-A)") (class "Default")
      (node (ref "R29") (pin "1") (pinfunction "1_1") (pintype "passive"))
      (node (ref "R9") (pin "1") (pinfunction "A_1") (pintype "passive"))
    )
    (net (code "113") (name "Net-(R9-E)") (class "Default")
      (node (ref "R11") (pin "2") (pinfunction "2_2") (pintype "passive"))
      (node (ref "R9") (pin "3") (pinfunction "E_3") (pintype "passive"))
    )
    (net (code "114") (name "Net-(R10-A)") (class "Default")
      (node (ref "R10") (pin "1") (pinfunction "A_1") (pintype "passive"))
      (node (ref "R30") (pin "1") (pinfunction "1_1") (pintype "passive"))
    )
    (net (code "115") (name "Net-(R10-E)") (class "Default")
      (node (ref "R10") (pin "3") (pinfunction "E_3") (pintype "passive"))
      (node (ref "R20") (pin "1") (pinfunction "1_1") (pintype "passive"))
    )
    (net (code "116") (name "Net-(R35-Pad2)") (class "Default")
      (node (ref "R35") (pin "2") (pinfunction "2_2") (pintype "passive"))
      (node (ref "SL3") (pin "4") (pinfunction "4_4") (pintype "passive"))
      (node (ref "U$1") (pin "OUT8") (pinfunction "OUT8_OUT8") (pintype "bidirectional"))
    )
    (net (code "117") (name "Net-(R60-Pad1)") (class "Default")
      (node (ref "R60") (pin "1") (pinfunction "1_1") (pintype "passive"))
      (node (ref "R71") (pin "2") (pinfunction "2_2") (pintype "passive"))
      (node (ref "SV7") (pin "1") (pinfunction "1_1") (pintype "passive"))
    )
    (net (code "118") (name "Net-(S6-+)") (class "Default")
      (node (ref "R62") (pin "1") (pinfunction "1_1") (pintype "passive"))
      (node (ref "S6") (pin "5") (pinfunction "+_5") (pintype "bidirectional"))
    )
    (net (code "119") (name "Net-(SL3-Pad3)") (class "Default")
      (node (ref "SL3") (pin "3") (pinfunction "3_3") (pintype "passive"))
      (node (ref "U$1") (pin "OUT7") (pinfunction "OUT7_OUT7") (pintype "bidirectional"))
    )
    (net (code "120") (name "Net-(X17B-S)") (class "Default")
      (node (ref "C51") (pin "1") (pinfunction "1_1") (pintype "passive"))
      (node (ref "R61") (pin "1") (pinfunction "1_1") (pintype "passive"))
      (node (ref "R71") (pin "1") (pinfunction "1_1") (pintype "passive"))
      (node (ref "S6") (pin "4") (pinfunction "4_4") (pintype "bidirectional"))
      (node (ref "X17") (pin "2") (pinfunction "S_2") (pintype "passive"))
    )
    (net (code "121") (name "VCC") (class "Default")
      (node (ref "C65") (pin "1") (pinfunction "1_1") (pintype "passive"))
      (node (ref "C68") (pin "1") (pinfunction "1_1") (pintype "passive"))
      (node (ref "C69") (pin "1") (pinfunction "1_1") (pintype "passive"))
      (node (ref "JMP6") (pin "2") (pinfunction "2_2") (pintype "passive"))
      (node (ref "Q3") (pin "1") (pinfunction "OE_1") (pintype "input"))
      (node (ref "Q3") (pin "4") (pinfunction "VCC_4") (pintype "power_in"))
      (node (ref "R66") (pin "1") (pinfunction "1_1") (pintype "passive"))
    )
    (net (code "122") (name "VDD") (class "Default")
      (node (ref "C1") (pin "1") (pinfunction "1_1") (pintype "passive"))
      (node (ref "C10") (pin "1") (pinfunction "1_1") (pintype "passive"))
      (node (ref "C4") (pin "2") (pinfunction "2_2") (pintype "passive"))
      (node (ref "C5") (pin "1") (pinfunction "1_1") (pintype "passive"))
      (node (ref "C58") (pin "1") (pinfunction "1_1") (pintype "passive"))
      (node (ref "C59") (pin "1") (pinfunction "1_1") (pintype "passive"))
      (node (ref "D1") (pin "C") (pinfunction "C_C") (pintype "passive"))
      (node (ref "IC16") (pin "3") (pinfunction "3_3") (pintype "bidirectional"))
      (node (ref "IC16") (pin "4") (pinfunction "4_4") (pintype "bidirectional"))
      (node (ref "IC2") (pin "2") (pinfunction "2_2") (pintype "passive"))
      (node (ref "IC4") (pin "3") (pinfunction "VO_3") (pintype "passive"))
      (node (ref "INP") (pin "8") (pinfunction "S_8") (pintype "passive"))
      (node (ref "J1") (pin "12") (pinfunction "12_12") (pintype "passive"))
      (node (ref "J2") (pin "2") (pinfunction "2_2") (pintype "passive"))
      (node (ref "JMP6") (pin "1") (pinfunction "1_1") (pintype "passive"))
      (node (ref "L1") (pin "1") (pinfunction "1_1") (pintype "passive"))
      (node (ref "L2") (pin "2") (pinfunction "2_2") (pintype "passive"))
      (node (ref "R33") (pin "2") (pinfunction "2_2") (pintype "passive"))
      (node (ref "R61") (pin "2") (pinfunction "2_2") (pintype "passive"))
      (node (ref "R66") (pin "2") (pinfunction "2_2") (pintype "passive"))
      (node (ref "REFVDD") (pin "TP") (pinfunction "TP_TP") (pintype "input"))
      (node (ref "SL4") (pin "2") (pinfunction "2_2") (pintype "passive"))
      (node (ref "SPI_IN") (pin "7") (pinfunction "S_7") (pintype "passive"))
      (node (ref "SPI_OUT") (pin "7") (pinfunction "S_7") (pintype "passive"))
      (node (ref "SV7") (pin "2") (pinfunction "2_2") (pintype "passive"))
      (node (ref "U$1") (pin "VCC") (pinfunction "VCC_VCC") (pintype "bidirectional"))
    )
    (net (code "123") (name "VSS") (class "Default")
      (node (ref "C1") (pin "2") (pinfunction "2_2") (pintype "passive"))
      (node (ref "C10") (pin "2") (pinfunction "2_2") (pintype "passive"))
      (node (ref "C11") (pin "2") (pinfunction "2_2") (pintype "passive"))
      (node (ref "C12") (pin "2") (pinfunction "2_2") (pintype "passive"))
      (node (ref "C4") (pin "1") (pinfunction "1_1") (pintype "passive"))
      (node (ref "C5") (pin "2") (pinfunction "2_2") (pintype "passive"))
      (node (ref "C51") (pin "2") (pinfunction "2_2") (pintype "passive"))
      (node (ref "C52") (pin "2") (pinfunction "2_2") (pintype "passive"))
      (node (ref "C53") (pin "2") (pinfunction "2_2") (pintype "passive"))
      (node (ref "C54") (pin "2") (pinfunction "2_2") (pintype "passive"))
      (node (ref "C57") (pin "2") (pinfunction "2_2") (pintype "passive"))
      (node (ref "C58") (pin "2") (pinfunction "2_2") (pintype "passive"))
      (node (ref "C59") (pin "2") (pinfunction "2_2") (pintype "passive"))
      (node (ref "C6") (pin "2") (pinfunction "2_2") (pintype "passive"))
      (node (ref "C60") (pin "2") (pinfunction "2_2") (pintype "passive"))
      (node (ref "C61") (pin "2") (pinfunction "2_2") (pintype "passive"))
      (node (ref "C62") (pin "2") (pinfunction "2_2") (pintype "passive"))
      (node (ref "C67") (pin "2") (pinfunction "2_2") (pintype "passive"))
      (node (ref "C7") (pin "2") (pinfunction "2_2") (pintype "passive"))
      (node (ref "C8") (pin "2") (pinfunction "2_2") (pintype "passive"))
      (node (ref "C9") (pin "2") (pinfunction "2_2") (pintype "passive"))
      (node (ref "D1") (pin "A") (pinfunction "A_A") (pintype "passive"))
      (node (ref "IC1") (pin "9") (pinfunction "GND_9") (pintype "power_in"))
      (node (ref "IC15") (pin "31") (pinfunction "VSS_2_31") (pintype "bidirectional"))
      (node (ref "IC15") (pin "6") (pinfunction "VSS_1_6") (pintype "bidirectional"))
      (node (ref "IC16") (pin "1") (pinfunction "1_1") (pintype "bidirectional"))
      (node (ref "IC16") (pin "2") (pinfunction "2_2") (pintype "bidirectional"))
      (node (ref "IC2") (pin "1") (pinfunction "1_1") (pintype "passive"))
      (node (ref "IC3") (pin "4") (pinfunction "GND_4") (pintype "power_in"))
      (node (ref "IC4") (pin "2") (pinfunction "GND_2") (pintype "passive"))
      (node (ref "IC5") (pin "2") (pinfunction "GND_2") (pintype "passive"))
      (node (ref "IC6") (pin "2") (pinfunction "GND_2") (pintype "passive"))
      (node (ref "INP") (pin "9") (pinfunction "S_9") (pintype "passive"))
      (node (ref "J1") (pin "11") (pinfunction "11_11") (pintype "passive"))
      (node (ref "J2") (pin "1") (pinfunction "1_1") (pintype "passive"))
      (node (ref "JMP5") (pin "1") (pinfunction "1_1") (pintype "passive"))
      (node (ref "LED1") (pin "C") (pinfunction "C_C") (pintype "passive"))
      (node (ref "LED2") (pin "C") (pinfunction "C_C") (pintype "passive"))
      (node (ref "LED3") (pin "C") (pinfunction "C_C") (pintype "passive"))
      (node (ref "LED4") (pin "C") (pinfunction "C_C") (pintype "passive"))
      (node (ref "LED5") (pin "C") (pinfunction "C_C") (pintype "passive"))
      (node (ref "LED8") (pin "C") (pinfunction "C_C") (pintype "passive"))
      (node (ref "OUTP") (pin "9") (pinfunction "S_9") (pintype "passive"))
      (node (ref "R21") (pin "2") (pinfunction "2_2") (pintype "passive"))
      (node (ref "R22") (pin "2") (pinfunction "2_2") (pintype "passive"))
      (node (ref "R23") (pin "2") (pinfunction "2_2") (pintype "passive"))
      (node (ref "R24") (pin "2") (pinfunction "2_2") (pintype "passive"))
      (node (ref "R25") (pin "2") (pinfunction "2_2") (pintype "passive"))
      (node (ref "R26") (pin "2") (pinfunction "2_2") (pintype "passive"))
      (node (ref "R27") (pin "2") (pinfunction "2_2") (pintype "passive"))
      (node (ref "R28") (pin "2") (pinfunction "2_2") (pintype "passive"))
      (node (ref "R29") (pin "2") (pinfunction "2_2") (pintype "passive"))
      (node (ref "R30") (pin "2") (pinfunction "2_2") (pintype "passive"))
      (node (ref "R67") (pin "2") (pinfunction "2_2") (pintype "passive"))
      (node (ref "REFVSS") (pin "TP") (pinfunction "TP_TP") (pintype "input"))
      (node (ref "RS-232-3") (pin "1") (pinfunction "1_1") (pintype "passive"))
      (node (ref "RS232-3") (pin "1") (pinfunction "1_1") (pintype "passive"))
      (node (ref "S6") (pin "2") (pinfunction "2_2") (pintype "bidirectional"))
      (node (ref "S6") (pin "6") (pinfunction "-_6") (pintype "bidirectional"))
      (node (ref "SL1") (pin "1") (pinfunction "1_1") (pintype "passive"))
      (node (ref "SL2") (pin "1") (pinfunction "1_1") (pintype "passive"))
      (node (ref "SL3") (pin "1") (pinfunction "1_1") (pintype "passive"))
      (node (ref "SL4") (pin "1") (pinfunction "1_1") (pintype "passive"))
      (node (ref "SPI_IN") (pin "8") (pinfunction "S_8") (pintype "passive"))
      (node (ref "SPI_OUT") (pin "8") (pinfunction "S_8") (pintype "passive"))
      (node (ref "SV7") (pin "3") (pinfunction "3_3") (pintype "passive"))
      (node (ref "SV8") (pin "1") (pinfunction "1_1") (pintype "passive"))
      (node (ref "U$1") (pin "GND") (pinfunction "GND_GND") (pintype "bidirectional"))
      (node (ref "X17") (pin "1") (pinfunction "S_1") (pintype "passive"))
    )
    (net (code "124") (name "unconnected-(IC2-Pad3)") (class "Default")
      (node (ref "IC2") (pin "3") (pinfunction "3_3") (pintype "passive"))
    )
    (net (code "125") (name "unconnected-(IC3-OPT-Pad3)") (class "Default")
      (node (ref "IC3") (pin "3") (pinfunction "OPT_3") (pintype "output"))
    )
    (net (code "126") (name "unconnected-(IC3-TRM-Pad5)") (class "Default")
      (node (ref "IC3") (pin "5") (pinfunction "TRM_5") (pintype "input"))
    )
    (net (code "127") (name "unconnected-(IC15-RF6-Pad14)") (class "Default")
      (node (ref "IC15") (pin "14") (pinfunction "RF6_14") (pintype "bidirectional"))
    )
    (net (code "128") (name "unconnected-(IC15-RF7-Pad15)") (class "Default")
      (node (ref "IC15") (pin "15") (pinfunction "RF7_15") (pintype "bidirectional"))
    )
    (net (code "129") (name "unconnected-(JMP5-Pad3)") (class "Default")
      (node (ref "JMP5") (pin "3") (pinfunction "3_3") (pintype "passive"))
    )
    (net (code "130") (name "unconnected-(JMP6-Pad3)") (class "Default")
      (node (ref "JMP6") (pin "3") (pinfunction "3_3") (pintype "passive"))
    )
    (net (code "131") (name "unconnected-(RS-232-3-Pad4)") (class "Default")
      (node (ref "RS-232-3") (pin "4") (pinfunction "4_4") (pintype "passive"))
    )
    (net (code "132") (name "unconnected-(RS232-3-Pad4)") (class "Default")
      (node (ref "RS232-3") (pin "4") (pinfunction "4_4") (pintype "passive"))
    )
    (net (code "133") (name "unconnected-(S6-Pad1)") (class "Default")
      (node (ref "S6") (pin "1") (pinfunction "1_1") (pintype "bidirectional"))
    )
    (net (code "134") (name "unconnected-(S6-Pad3)") (class "Default")
      (node (ref "S6") (pin "3") (pinfunction "3_3") (pintype "bidirectional"))
    )
    (net (code "135") (name "unconnected-(SV7-Pad6)") (class "Default")
      (node (ref "SV7") (pin "6") (pinfunction "6_6") (pintype "passive"))
    )
  )
)
